# Voltage_Current_Sensor_V2.net
KiCad netlist of a schematic drawn in Altium Designer
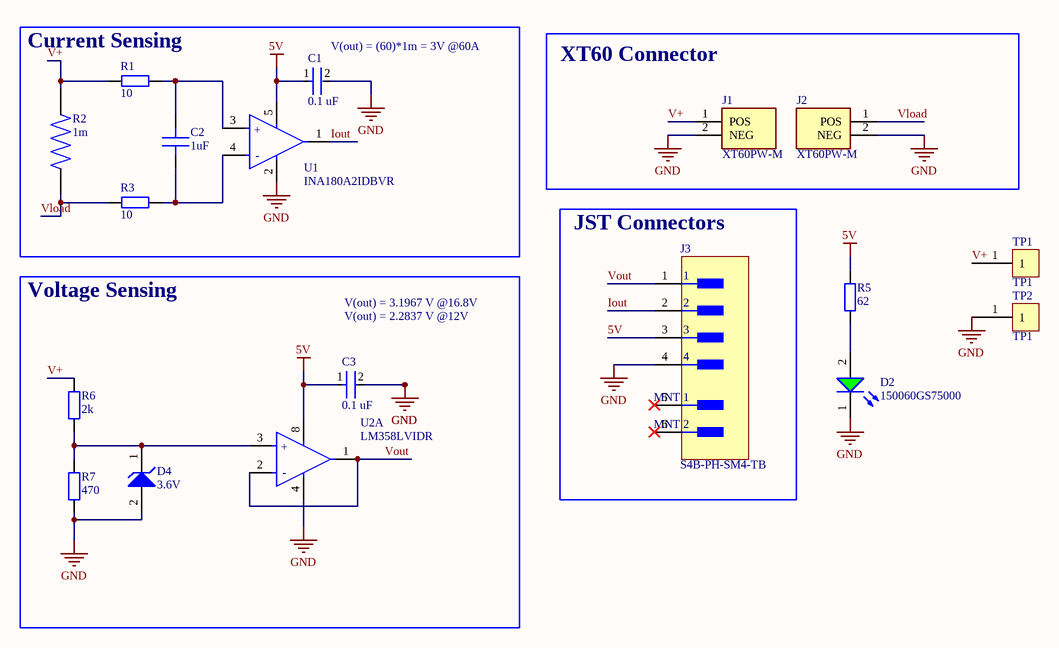
[diagram p0: Voltage & Current Sensor V2.SchDoc]

(export (version "E")
  (design (tool "Eeschema 10.0.6"))
  (components
    (comp (ref "C1")
      (value "0.1 uF")
      (footprint "FP-CL17-IPC_C")
      (description "Cap Ceramic 100nF 10V X7R ±10% SMD 0402 +125°C Paper T/RCL05B104KP5NNNC")
      (fields (field (name "TOLERANCE") "10%"))
      (libsource (lib "Altium Content Vault") (part "b4654b650e69147ec39a6b967a45e02"))
    )
    (comp (ref "C2")
      (value "1uF")
      (footprint "IPC C C0603 NO SILK")
      (description "Generic CAP 0603")
      (libsource (lib "University of British Columbia") (part "Generic CAP 1210"))
    )
    (comp (ref "C3")
      (value "0.1 uF")
      (footprint "FP-CL17-IPC_C")
      (description "Cap Ceramic 100nF 10V X7R ±10% SMD 0402 +125°C Paper T/RCL05B104KP5NNNC")
      (fields (field (name "TOLERANCE") "10%"))
      (libsource (lib "Altium Content Vault") (part "b4654b650e69147ec39a6b967a45e02"))
    )
    (comp (ref "D2")
      (value "150060GS75000")
      (footprint "WL-SMCW_0603_150060xx75000")
      (description "430mcd Colorless transparence 520nm Emerald 140° LED0603 Light Emitting Diodes (LED) ROHS")
      (libsource (lib "Altium Content Vault") (part "LED_Green_2A-1K"))
    )
    (comp (ref "D4")
      (value "3.6V")
      (footprint "ONSC-SOD-123-2-425-04_V")
      (fields (field (name "MANUFACTURER") "On Semiconductor") (field (name "PARTNUMBER") "MMSZ4685T1G"))
      (libsource (lib "Altium Content Vault") (part "ONSC-K1A2-2"))
    )
    (comp (ref "J1")
      (value "XT60PW-M")
      (footprint "AMASS_XT60PW-M")
      (description "Socket, DC supply, male, PIN: 2")
      (fields (field (name "MF") "AMASS"))
      (libsource (lib "") (part "XT60PW-M_1"))
    )
    (comp (ref "J2")
      (value "XT60PW-M")
      (footprint "AMASS_XT60PW-M")
      (description "Socket, DC supply, male, PIN: 2")
      (fields (field (name "MF") "AMASS"))
      (libsource (lib "University of British Columbia") (part "XT60PW-M"))
    )
    (comp (ref "J3")
      (value "S4B-PH-SM4-TB")
      (footprint "FP-S4B-PH-SM4-TB-MFG")
      (description "S4B-PH-SM4-TB Header S4B-PH-SM4-TB, 2.00mm, 4-contacts, side entry, SMT, /1000/reel")
      (libsource (lib "Altium Content Vault") (part "S4B-PH-SM4-TB"))
    )
    (comp (ref "R1")
      (value "10")
      (footprint "IPC C R0603 NO SILK")
      (description "Generic RES 0603")
      (libsource (lib "University of British Columbia") (part "Generic RES 0603"))
    )
    (comp (ref "R2")
      (value "1m")
      (footprint "RESC10052X105N")
      (description "Res Metal Film 3921 1mOhm 1% 4W Â±75ppm/Â°C Molded SMD Emboss T/R PSR400ITQFH1L00")
      (fields (field (name "MP") "PSR400ITQFH1L00"))
      (libsource (lib "PSR400ITQFH1L00") (part "PSR400ITQFH1L00"))
    )
    (comp (ref "R3")
      (value "10")
      (footprint "IPC C R0603 NO SILK")
      (description "Generic RES 0603")
      (libsource (lib "University of British Columbia") (part "Generic RES 0603"))
    )
    (comp (ref "R5")
      (value "62")
      (footprint "IPC C R0603 NO SILK")
      (description "Generic RES 0603")
      (libsource (lib "University of British Columbia") (part "Generic RES 0603"))
    )
    (comp (ref "R6")
      (value "2k")
      (footprint "IPC C R0402 NO SILK")
      (description "Generic RES 0402")
      (libsource (lib "University of British Columbia") (part "Generic RES 0603"))
    )
    (comp (ref "R7")
      (value "470")
      (footprint "IPC C R0402 NO SILK")
      (description "Generic RES 0402")
      (libsource (lib "University of British Columbia") (part "Generic RES 0603"))
    )
    (comp (ref "TP1")
      (value "TP1")
      (footprint "TP1")
      (description "Testpoint double sided")
      (libsource (lib "University of British Columbia") (part "TP1"))
    )
    (comp (ref "TP2")
      (value "TP1")
      (footprint "TP1")
      (description "Testpoint double sided")
      (libsource (lib "University of British Columbia") (part "TP1"))
    )
    (comp (ref "U1")
      (value "INA180A2IDBVR")
      (footprint "FP-DBV0005A-MFG")
      (description "IC CURR SENSE 1 CIRCUIT SOT23-5 50V/V")
      (libsource (lib "Altium Content Vault") (part "0a55cf1a948ad01a3239aec1b7efad0"))
    )
    (comp (ref "U2")
      (value "LM358LVIDR")
      (footprint "FP-D0008A-MFG")
      (description "IC OPAMP GP 2 CIRCUIT 8SOIC")
      (libsource (lib "Altium Content Vault") (part "d5b36c1049528187b1d2197d5d58d7e"))
    )
  )
  (nets
    (net (code "1") (name "/Iout") (class "Default")
      (node (ref "J3") (pin "2") (pinfunction "2_2") (pintype "passive"))
      (node (ref "U1") (pin "1") (pinfunction "OUT_1") (pintype "passive"))
    )
    (net (code "2") (name "/V+") (class "Default")
      (node (ref "J1") (pin "1") (pinfunction "POS_1") (pintype "passive"))
      (node (ref "R1") (pin "1") (pinfunction "1_1") (pintype "passive"))
      (node (ref "R2") (pin "2") (pinfunction "2_2") (pintype "passive"))
      (node (ref "R6") (pin "2") (pinfunction "2_2") (pintype "passive"))
      (node (ref "TP1") (pin "1") (pinfunction "1_1") (pintype "passive"))
    )
    (net (code "3") (name "/Vload") (class "Default")
      (node (ref "J2") (pin "1") (pinfunction "POS_1") (pintype "passive"))
      (node (ref "R2") (pin "1") (pinfunction "1_1") (pintype "passive"))
      (node (ref "R3") (pin "1") (pinfunction "1_1") (pintype "passive"))
    )
    (net (code "4") (name "/Vout") (class "Default")
      (node (ref "J3") (pin "1") (pinfunction "1_1") (pintype "passive"))
      (node (ref "U2") (pin "1") (pinfunction "OUT1_1") (pintype "passive"))
      (node (ref "U2") (pin "2") (pinfunction "IN1-_2") (pintype "tri_state"))
    )
    (net (code "5") (name "5V") (class "Default")
      (node (ref "C1") (pin "1") (pinfunction "1_1") (pintype "passive"))
      (node (ref "C3") (pin "1") (pinfunction "1_1") (pintype "passive"))
      (node (ref "J3") (pin "3") (pinfunction "3_3") (pintype "passive"))
      (node (ref "R5") (pin "2") (pinfunction "2_2") (pintype "passive"))
      (node (ref "U1") (pin "5") (pinfunction "VS_5") (pintype "power_in"))
      (node (ref "U2") (pin "8") (pinfunction "V+_8") (pintype "power_in"))
    )
    (net (code "6") (name "GND") (class "Default")
      (node (ref "C1") (pin "2") (pinfunction "2_2") (pintype "passive"))
      (node (ref "C3") (pin "2") (pinfunction "2_2") (pintype "passive"))
      (node (ref "D2") (pin "1") (pinfunction "K_1") (pintype "passive"))
      (node (ref "D4") (pin "2") (pinfunction "A_2") (pintype "passive"))
      (node (ref "J1") (pin "2") (pinfunction "NEG_2") (pintype "passive"))
      (node (ref "J2") (pin "2") (pinfunction "NEG_2") (pintype "passive"))
      (node (ref "J3") (pin "4") (pinfunction "4_4") (pintype "passive"))
      (node (ref "R7") (pin "1") (pinfunction "1_1") (pintype "passive"))
      (node (ref "TP2") (pin "1") (pinfunction "1_1") (pintype "passive"))
      (node (ref "U1") (pin "2") (pinfunction "GND_2") (pintype "power_in"))
      (node (ref "U2") (pin "4") (pinfunction "V-_4") (pintype "power_in"))
    )
    (net (code "7") (name "Net-(D2-A)") (class "Default")
      (node (ref "D2") (pin "2") (pinfunction "A_2") (pintype "passive"))
      (node (ref "R5") (pin "1") (pinfunction "1_1") (pintype "passive"))
    )
    (net (code "8") (name "Net-(D4-K)") (class "Default")
      (node (ref "D4") (pin "1") (pinfunction "K_1") (pintype "passive"))
      (node (ref "R6") (pin "1") (pinfunction "1_1") (pintype "passive"))
      (node (ref "R7") (pin "2") (pinfunction "2_2") (pintype "passive"))
      (node (ref "U2") (pin "3") (pinfunction "IN1+_3") (pintype "tri_state"))
    )
    (net (code "9") (name "Net-(U1-IN+)") (class "Default")
      (node (ref "C2") (pin "2") (pinfunction "2_2") (pintype "passive"))
      (node (ref "R1") (pin "2") (pinfunction "2_2") (pintype "passive"))
      (node (ref "U1") (pin "3") (pinfunction "IN+_3") (pintype "tri_state"))
    )
    (net (code "10") (name "Net-(U1-IN-)") (class "Default")
      (node (ref "C2") (pin "1") (pinfunction "1_1") (pintype "passive"))
      (node (ref "R3") (pin "2") (pinfunction "2_2") (pintype "passive"))
      (node (ref "U1") (pin "4") (pinfunction "IN-_4") (pintype "tri_state"))
    )
    (net (code "11") (name "unconnected-(J3-MNT_1-Pad5)") (class "Default")
      (node (ref "J3") (pin "5") (pinfunction "MNT_1_5") (pintype "passive+no_connect"))
    )
    (net (code "12") (name "unconnected-(J3-MNT_2-Pad6)") (class "Default")
      (node (ref "J3") (pin "6") (pinfunction "MNT_2_6") (pintype "passive+no_connect"))
    )
  )
)
